# jkGate.net
KiCad netlist of a schematic drawn in EAGLE
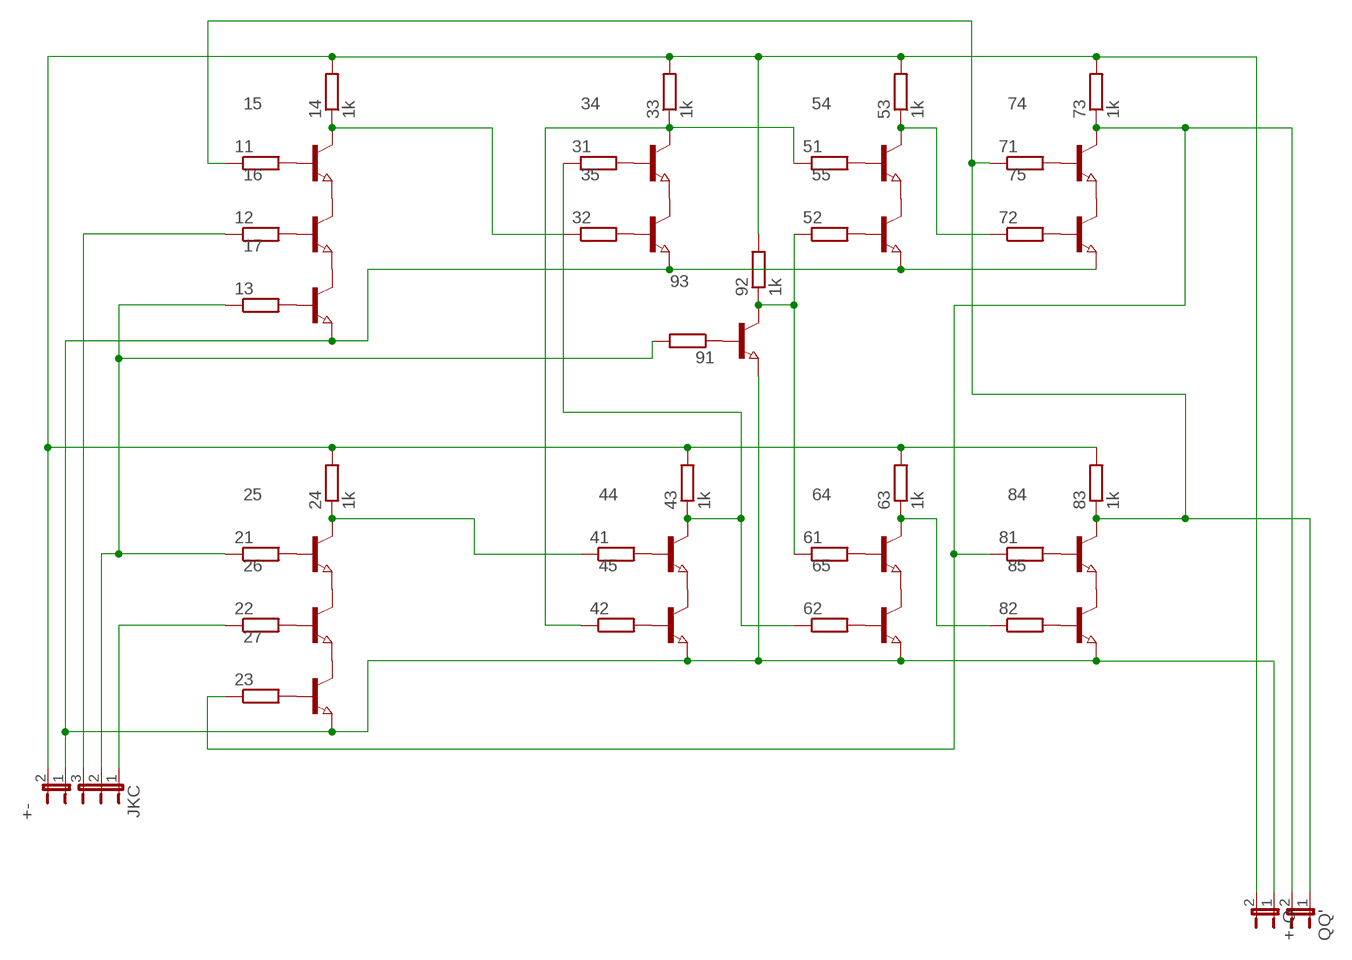
[diagram p0: schematic, sheet 1]

(export (version "E")
  (design (tool "Eeschema 10.0.6"))
  (components
    (comp (ref "+-")
      (value "JP1E")
      (footprint "eagle-import:JP1")
      (libsource (lib "eagle-import") (part "JP1E"))
    )
    (comp (ref "+-O")
      (value "JP1E")
      (footprint "eagle-import:JP1")
      (libsource (lib "eagle-import") (part "JP1E"))
    )
    (comp (ref "11")
      (value "R-EU_R1206")
      (footprint "eagle-import:R1206")
      (libsource (lib "eagle-import") (part "R-EU_R1206"))
    )
    (comp (ref "12")
      (value "R-EU_R1206")
      (footprint "eagle-import:R1206")
      (libsource (lib "eagle-import") (part "R-EU_R1206"))
    )
    (comp (ref "13")
      (value "R-EU_R1206")
      (footprint "eagle-import:R1206")
      (libsource (lib "eagle-import") (part "R-EU_R1206"))
    )
    (comp (ref "14")
      (value "1k")
      (footprint "eagle-import:R1206")
      (libsource (lib "eagle-import") (part "R-EU_R1206"))
    )
    (comp (ref "15")
      (value "NPN-TRANSISTOR_SOT23")
      (footprint "eagle-import:SOT23")
      (libsource (lib "eagle-import") (part "NPN-TRANSISTOR_SOT23"))
    )
    (comp (ref "16")
      (value "NPN-TRANSISTOR_SOT23")
      (footprint "eagle-import:SOT23")
      (libsource (lib "eagle-import") (part "NPN-TRANSISTOR_SOT23"))
    )
    (comp (ref "17")
      (value "NPN-TRANSISTOR_SOT23")
      (footprint "eagle-import:SOT23")
      (libsource (lib "eagle-import") (part "NPN-TRANSISTOR_SOT23"))
    )
    (comp (ref "21")
      (value "R-EU_R1206")
      (footprint "eagle-import:R1206")
      (libsource (lib "eagle-import") (part "R-EU_R1206"))
    )
    (comp (ref "22")
      (value "R-EU_R1206")
      (footprint "eagle-import:R1206")
      (libsource (lib "eagle-import") (part "R-EU_R1206"))
    )
    (comp (ref "23")
      (value "R-EU_R1206")
      (footprint "eagle-import:R1206")
      (libsource (lib "eagle-import") (part "R-EU_R1206"))
    )
    (comp (ref "24")
      (value "1k")
      (footprint "eagle-import:R1206")
      (libsource (lib "eagle-import") (part "R-EU_R1206"))
    )
    (comp (ref "25")
      (value "NPN-TRANSISTOR_SOT23")
      (footprint "eagle-import:SOT23")
      (libsource (lib "eagle-import") (part "NPN-TRANSISTOR_SOT23"))
    )
    (comp (ref "26")
      (value "NPN-TRANSISTOR_SOT23")
      (footprint "eagle-import:SOT23")
      (libsource (lib "eagle-import") (part "NPN-TRANSISTOR_SOT23"))
    )
    (comp (ref "27")
      (value "NPN-TRANSISTOR_SOT23")
      (footprint "eagle-import:SOT23")
      (libsource (lib "eagle-import") (part "NPN-TRANSISTOR_SOT23"))
    )
    (comp (ref "31")
      (value "R-EU_R1206")
      (footprint "eagle-import:R1206")
      (libsource (lib "eagle-import") (part "R-EU_R1206"))
    )
    (comp (ref "32")
      (value "R-EU_R1206")
      (footprint "eagle-import:R1206")
      (libsource (lib "eagle-import") (part "R-EU_R1206"))
    )
    (comp (ref "33")
      (value "1k")
      (footprint "eagle-import:R1206")
      (libsource (lib "eagle-import") (part "R-EU_R1206"))
    )
    (comp (ref "34")
      (value "NPN-TRANSISTOR_SOT23")
      (footprint "eagle-import:SOT23")
      (libsource (lib "eagle-import") (part "NPN-TRANSISTOR_SOT23"))
    )
    (comp (ref "35")
      (value "NPN-TRANSISTOR_SOT23")
      (footprint "eagle-import:SOT23")
      (libsource (lib "eagle-import") (part "NPN-TRANSISTOR_SOT23"))
    )
    (comp (ref "41")
      (value "R-EU_R1206")
      (footprint "eagle-import:R1206")
      (libsource (lib "eagle-import") (part "R-EU_R1206"))
    )
    (comp (ref "42")
      (value "R-EU_R1206")
      (footprint "eagle-import:R1206")
      (libsource (lib "eagle-import") (part "R-EU_R1206"))
    )
    (comp (ref "43")
      (value "1k")
      (footprint "eagle-import:R1206")
      (libsource (lib "eagle-import") (part "R-EU_R1206"))
    )
    (comp (ref "44")
      (value "NPN-TRANSISTOR_SOT23")
      (footprint "eagle-import:SOT23")
      (libsource (lib "eagle-import") (part "NPN-TRANSISTOR_SOT23"))
    )
    (comp (ref "45")
      (value "NPN-TRANSISTOR_SOT23")
      (footprint "eagle-import:SOT23")
      (libsource (lib "eagle-import") (part "NPN-TRANSISTOR_SOT23"))
    )
    (comp (ref "51")
      (value "R-EU_R1206")
      (footprint "eagle-import:R1206")
      (libsource (lib "eagle-import") (part "R-EU_R1206"))
    )
    (comp (ref "52")
      (value "R-EU_R1206")
      (footprint "eagle-import:R1206")
      (libsource (lib "eagle-import") (part "R-EU_R1206"))
    )
    (comp (ref "53")
      (value "1k")
      (footprint "eagle-import:R1206")
      (libsource (lib "eagle-import") (part "R-EU_R1206"))
    )
    (comp (ref "54")
      (value "NPN-TRANSISTOR_SOT23")
      (footprint "eagle-import:SOT23")
      (libsource (lib "eagle-import") (part "NPN-TRANSISTOR_SOT23"))
    )
    (comp (ref "55")
      (value "NPN-TRANSISTOR_SOT23")
      (footprint "eagle-import:SOT23")
      (libsource (lib "eagle-import") (part "NPN-TRANSISTOR_SOT23"))
    )
    (comp (ref "61")
      (value "R-EU_R1206")
      (footprint "eagle-import:R1206")
      (libsource (lib "eagle-import") (part "R-EU_R1206"))
    )
    (comp (ref "62")
      (value "R-EU_R1206")
      (footprint "eagle-import:R1206")
      (libsource (lib "eagle-import") (part "R-EU_R1206"))
    )
    (comp (ref "63")
      (value "1k")
      (footprint "eagle-import:R1206")
      (libsource (lib "eagle-import") (part "R-EU_R1206"))
    )
    (comp (ref "64")
      (value "NPN-TRANSISTOR_SOT23")
      (footprint "eagle-import:SOT23")
      (libsource (lib "eagle-import") (part "NPN-TRANSISTOR_SOT23"))
    )
    (comp (ref "65")
      (value "NPN-TRANSISTOR_SOT23")
      (footprint "eagle-import:SOT23")
      (libsource (lib "eagle-import") (part "NPN-TRANSISTOR_SOT23"))
    )
    (comp (ref "71")
      (value "R-EU_R1206")
      (footprint "eagle-import:R1206")
      (libsource (lib "eagle-import") (part "R-EU_R1206"))
    )
    (comp (ref "72")
      (value "R-EU_R1206")
      (footprint "eagle-import:R1206")
      (libsource (lib "eagle-import") (part "R-EU_R1206"))
    )
    (comp (ref "73")
      (value "1k")
      (footprint "eagle-import:R1206")
      (libsource (lib "eagle-import") (part "R-EU_R1206"))
    )
    (comp (ref "74")
      (value "NPN-TRANSISTOR_SOT23")
      (footprint "eagle-import:SOT23")
      (libsource (lib "eagle-import") (part "NPN-TRANSISTOR_SOT23"))
    )
    (comp (ref "75")
      (value "NPN-TRANSISTOR_SOT23")
      (footprint "eagle-import:SOT23")
      (libsource (lib "eagle-import") (part "NPN-TRANSISTOR_SOT23"))
    )
    (comp (ref "81")
      (value "R-EU_R1206")
      (footprint "eagle-import:R1206")
      (libsource (lib "eagle-import") (part "R-EU_R1206"))
    )
    (comp (ref "82")
      (value "R-EU_R1206")
      (footprint "eagle-import:R1206")
      (libsource (lib "eagle-import") (part "R-EU_R1206"))
    )
    (comp (ref "83")
      (value "1k")
      (footprint "eagle-import:R1206")
      (libsource (lib "eagle-import") (part "R-EU_R1206"))
    )
    (comp (ref "84")
      (value "NPN-TRANSISTOR_SOT23")
      (footprint "eagle-import:SOT23")
      (libsource (lib "eagle-import") (part "NPN-TRANSISTOR_SOT23"))
    )
    (comp (ref "85")
      (value "NPN-TRANSISTOR_SOT23")
      (footprint "eagle-import:SOT23")
      (libsource (lib "eagle-import") (part "NPN-TRANSISTOR_SOT23"))
    )
    (comp (ref "91")
      (value "R-EU_R1206")
      (footprint "eagle-import:R1206")
      (libsource (lib "eagle-import") (part "R-EU_R1206"))
    )
    (comp (ref "92")
      (value "1k")
      (footprint "eagle-import:R1206")
      (libsource (lib "eagle-import") (part "R-EU_R1206"))
    )
    (comp (ref "93")
      (value "NPN-TRANSISTOR_SOT23")
      (footprint "eagle-import:SOT23")
      (libsource (lib "eagle-import") (part "NPN-TRANSISTOR_SOT23"))
    )
    (comp (ref "JKC")
      (value "JP2E")
      (footprint "eagle-import:JP2")
      (libsource (lib "eagle-import") (part "JP2E"))
    )
    (comp (ref "QQ'")
      (value "JP1E")
      (footprint "eagle-import:JP1")
      (libsource (lib "eagle-import") (part "JP1E"))
    )
  )
  (nets
    (net (code "1") (name "Net-(+--Pad2)") (class "Default")
      (node (ref "+-") (pin "2") (pinfunction "2_2") (pintype "passive"))
      (node (ref "+-O") (pin "2") (pinfunction "2_2") (pintype "passive"))
      (node (ref "14") (pin "2") (pinfunction "2_2") (pintype "passive"))
      (node (ref "24") (pin "2") (pinfunction "2_2") (pintype "passive"))
      (node (ref "33") (pin "2") (pinfunction "2_2") (pintype "passive"))
      (node (ref "43") (pin "2") (pinfunction "2_2") (pintype "passive"))
      (node (ref "53") (pin "2") (pinfunction "2_2") (pintype "passive"))
      (node (ref "63") (pin "2") (pinfunction "2_2") (pintype "passive"))
      (node (ref "73") (pin "2") (pinfunction "2_2") (pintype "passive"))
      (node (ref "83") (pin "2") (pinfunction "2_2") (pintype "passive"))
      (node (ref "92") (pin "2") (pinfunction "2_2") (pintype "passive"))
    )
    (net (code "2") (name "Net-(12-Pad1)") (class "Default")
      (node (ref "12") (pin "1") (pinfunction "1_1") (pintype "passive"))
      (node (ref "JKC") (pin "3") (pinfunction "3_3") (pintype "passive"))
    )
    (net (code "3") (name "Net-(13-Pad1)") (class "Default")
      (node (ref "13") (pin "1") (pinfunction "1_1") (pintype "passive"))
      (node (ref "21") (pin "1") (pinfunction "1_1") (pintype "passive"))
      (node (ref "91") (pin "2") (pinfunction "2_2") (pintype "passive"))
      (node (ref "JKC") (pin "2") (pinfunction "2_2") (pintype "passive"))
    )
    (net (code "4") (name "Net-(15-B)") (class "Default")
      (node (ref "11") (pin "2") (pinfunction "2_2") (pintype "passive"))
      (node (ref "15") (pin "1") (pinfunction "B_1") (pintype "passive"))
    )
    (net (code "5") (name "Net-(15-C)") (class "Default")
      (node (ref "14") (pin "1") (pinfunction "1_1") (pintype "passive"))
      (node (ref "15") (pin "3") (pinfunction "C_3") (pintype "passive"))
      (node (ref "32") (pin "1") (pinfunction "1_1") (pintype "passive"))
    )
    (net (code "6") (name "Net-(15-E)") (class "Default")
      (node (ref "15") (pin "2") (pinfunction "E_2") (pintype "passive"))
      (node (ref "16") (pin "3") (pinfunction "C_3") (pintype "passive"))
    )
    (net (code "7") (name "Net-(16-B)") (class "Default")
      (node (ref "12") (pin "2") (pinfunction "2_2") (pintype "passive"))
      (node (ref "16") (pin "1") (pinfunction "B_1") (pintype "passive"))
    )
    (net (code "8") (name "Net-(16-E)") (class "Default")
      (node (ref "16") (pin "2") (pinfunction "E_2") (pintype "passive"))
      (node (ref "17") (pin "3") (pinfunction "C_3") (pintype "passive"))
    )
    (net (code "9") (name "Net-(17-B)") (class "Default")
      (node (ref "13") (pin "2") (pinfunction "2_2") (pintype "passive"))
      (node (ref "17") (pin "1") (pinfunction "B_1") (pintype "passive"))
    )
    (net (code "10") (name "Net-(17-E)") (class "Default")
      (node (ref "+-") (pin "1") (pinfunction "1_1") (pintype "passive"))
      (node (ref "+-O") (pin "1") (pinfunction "1_1") (pintype "passive"))
      (node (ref "17") (pin "2") (pinfunction "E_2") (pintype "passive"))
      (node (ref "27") (pin "2") (pinfunction "E_2") (pintype "passive"))
      (node (ref "35") (pin "2") (pinfunction "E_2") (pintype "passive"))
      (node (ref "45") (pin "2") (pinfunction "E_2") (pintype "passive"))
      (node (ref "55") (pin "2") (pinfunction "E_2") (pintype "passive"))
      (node (ref "65") (pin "2") (pinfunction "E_2") (pintype "passive"))
      (node (ref "75") (pin "2") (pinfunction "E_2") (pintype "passive"))
      (node (ref "85") (pin "2") (pinfunction "E_2") (pintype "passive"))
      (node (ref "93") (pin "2") (pinfunction "E_2") (pintype "passive"))
    )
    (net (code "11") (name "Net-(22-Pad1)") (class "Default")
      (node (ref "22") (pin "1") (pinfunction "1_1") (pintype "passive"))
      (node (ref "JKC") (pin "1") (pinfunction "1_1") (pintype "passive"))
    )
    (net (code "12") (name "Net-(25-B)") (class "Default")
      (node (ref "21") (pin "2") (pinfunction "2_2") (pintype "passive"))
      (node (ref "25") (pin "1") (pinfunction "B_1") (pintype "passive"))
    )
    (net (code "13") (name "Net-(25-C)") (class "Default")
      (node (ref "24") (pin "1") (pinfunction "1_1") (pintype "passive"))
      (node (ref "25") (pin "3") (pinfunction "C_3") (pintype "passive"))
      (node (ref "41") (pin "1") (pinfunction "1_1") (pintype "passive"))
    )
    (net (code "14") (name "Net-(25-E)") (class "Default")
      (node (ref "25") (pin "2") (pinfunction "E_2") (pintype "passive"))
      (node (ref "26") (pin "3") (pinfunction "C_3") (pintype "passive"))
    )
    (net (code "15") (name "Net-(26-B)") (class "Default")
      (node (ref "22") (pin "2") (pinfunction "2_2") (pintype "passive"))
      (node (ref "26") (pin "1") (pinfunction "B_1") (pintype "passive"))
    )
    (net (code "16") (name "Net-(26-E)") (class "Default")
      (node (ref "26") (pin "2") (pinfunction "E_2") (pintype "passive"))
      (node (ref "27") (pin "3") (pinfunction "C_3") (pintype "passive"))
    )
    (net (code "17") (name "Net-(27-B)") (class "Default")
      (node (ref "23") (pin "2") (pinfunction "2_2") (pintype "passive"))
      (node (ref "27") (pin "1") (pinfunction "B_1") (pintype "passive"))
    )
    (net (code "18") (name "Net-(34-B)") (class "Default")
      (node (ref "31") (pin "2") (pinfunction "2_2") (pintype "passive"))
      (node (ref "34") (pin "1") (pinfunction "B_1") (pintype "passive"))
    )
    (net (code "19") (name "Net-(34-C)") (class "Default")
      (node (ref "33") (pin "1") (pinfunction "1_1") (pintype "passive"))
      (node (ref "34") (pin "3") (pinfunction "C_3") (pintype "passive"))
      (node (ref "42") (pin "1") (pinfunction "1_1") (pintype "passive"))
      (node (ref "51") (pin "1") (pinfunction "1_1") (pintype "passive"))
    )
    (net (code "20") (name "Net-(34-E)") (class "Default")
      (node (ref "34") (pin "2") (pinfunction "E_2") (pintype "passive"))
      (node (ref "35") (pin "3") (pinfunction "C_3") (pintype "passive"))
    )
    (net (code "21") (name "Net-(35-B)") (class "Default")
      (node (ref "32") (pin "2") (pinfunction "2_2") (pintype "passive"))
      (node (ref "35") (pin "1") (pinfunction "B_1") (pintype "passive"))
    )
    (net (code "22") (name "Net-(44-B)") (class "Default")
      (node (ref "41") (pin "2") (pinfunction "2_2") (pintype "passive"))
      (node (ref "44") (pin "1") (pinfunction "B_1") (pintype "passive"))
    )
    (net (code "23") (name "Net-(44-C)") (class "Default")
      (node (ref "31") (pin "1") (pinfunction "1_1") (pintype "passive"))
      (node (ref "43") (pin "1") (pinfunction "1_1") (pintype "passive"))
      (node (ref "44") (pin "3") (pinfunction "C_3") (pintype "passive"))
      (node (ref "62") (pin "1") (pinfunction "1_1") (pintype "passive"))
    )
    (net (code "24") (name "Net-(44-E)") (class "Default")
      (node (ref "44") (pin "2") (pinfunction "E_2") (pintype "passive"))
      (node (ref "45") (pin "3") (pinfunction "C_3") (pintype "passive"))
    )
    (net (code "25") (name "Net-(45-B)") (class "Default")
      (node (ref "42") (pin "2") (pinfunction "2_2") (pintype "passive"))
      (node (ref "45") (pin "1") (pinfunction "B_1") (pintype "passive"))
    )
    (net (code "26") (name "Net-(54-B)") (class "Default")
      (node (ref "51") (pin "2") (pinfunction "2_2") (pintype "passive"))
      (node (ref "54") (pin "1") (pinfunction "B_1") (pintype "passive"))
    )
    (net (code "27") (name "Net-(54-C)") (class "Default")
      (node (ref "53") (pin "1") (pinfunction "1_1") (pintype "passive"))
      (node (ref "54") (pin "3") (pinfunction "C_3") (pintype "passive"))
      (node (ref "72") (pin "1") (pinfunction "1_1") (pintype "passive"))
    )
    (net (code "28") (name "Net-(54-E)") (class "Default")
      (node (ref "54") (pin "2") (pinfunction "E_2") (pintype "passive"))
      (node (ref "55") (pin "3") (pinfunction "C_3") (pintype "passive"))
    )
    (net (code "29") (name "Net-(55-B)") (class "Default")
      (node (ref "52") (pin "2") (pinfunction "2_2") (pintype "passive"))
      (node (ref "55") (pin "1") (pinfunction "B_1") (pintype "passive"))
    )
    (net (code "30") (name "Net-(64-B)") (class "Default")
      (node (ref "61") (pin "2") (pinfunction "2_2") (pintype "passive"))
      (node (ref "64") (pin "1") (pinfunction "B_1") (pintype "passive"))
    )
    (net (code "31") (name "Net-(64-C)") (class "Default")
      (node (ref "63") (pin "1") (pinfunction "1_1") (pintype "passive"))
      (node (ref "64") (pin "3") (pinfunction "C_3") (pintype "passive"))
      (node (ref "82") (pin "1") (pinfunction "1_1") (pintype "passive"))
    )
    (net (code "32") (name "Net-(64-E)") (class "Default")
      (node (ref "64") (pin "2") (pinfunction "E_2") (pintype "passive"))
      (node (ref "65") (pin "3") (pinfunction "C_3") (pintype "passive"))
    )
    (net (code "33") (name "Net-(65-B)") (class "Default")
      (node (ref "62") (pin "2") (pinfunction "2_2") (pintype "passive"))
      (node (ref "65") (pin "1") (pinfunction "B_1") (pintype "passive"))
    )
    (net (code "34") (name "Net-(74-B)") (class "Default")
      (node (ref "71") (pin "2") (pinfunction "2_2") (pintype "passive"))
      (node (ref "74") (pin "1") (pinfunction "B_1") (pintype "passive"))
    )
    (net (code "35") (name "Net-(74-C)") (class "Default")
      (node (ref "23") (pin "1") (pinfunction "1_1") (pintype "passive"))
      (node (ref "73") (pin "1") (pinfunction "1_1") (pintype "passive"))
      (node (ref "74") (pin "3") (pinfunction "C_3") (pintype "passive"))
      (node (ref "81") (pin "1") (pinfunction "1_1") (pintype "passive"))
      (node (ref "QQ'") (pin "2") (pinfunction "2_2") (pintype "passive"))
    )
    (net (code "36") (name "Net-(74-E)") (class "Default")
      (node (ref "74") (pin "2") (pinfunction "E_2") (pintype "passive"))
      (node (ref "75") (pin "3") (pinfunction "C_3") (pintype "passive"))
    )
    (net (code "37") (name "Net-(75-B)") (class "Default")
      (node (ref "72") (pin "2") (pinfunction "2_2") (pintype "passive"))
      (node (ref "75") (pin "1") (pinfunction "B_1") (pintype "passive"))
    )
    (net (code "38") (name "Net-(84-B)") (class "Default")
      (node (ref "81") (pin "2") (pinfunction "2_2") (pintype "passive"))
      (node (ref "84") (pin "1") (pinfunction "B_1") (pintype "passive"))
    )
    (net (code "39") (name "Net-(84-C)") (class "Default")
      (node (ref "11") (pin "1") (pinfunction "1_1") (pintype "passive"))
      (node (ref "71") (pin "1") (pinfunction "1_1") (pintype "passive"))
      (node (ref "83") (pin "1") (pinfunction "1_1") (pintype "passive"))
      (node (ref "84") (pin "3") (pinfunction "C_3") (pintype "passive"))
      (node (ref "QQ'") (pin "1") (pinfunction "1_1") (pintype "passive"))
    )
    (net (code "40") (name "Net-(84-E)") (class "Default")
      (node (ref "84") (pin "2") (pinfunction "E_2") (pintype "passive"))
      (node (ref "85") (pin "3") (pinfunction "C_3") (pintype "passive"))
    )
    (net (code "41") (name "Net-(85-B)") (class "Default")
      (node (ref "82") (pin "2") (pinfunction "2_2") (pintype "passive"))
      (node (ref "85") (pin "1") (pinfunction "B_1") (pintype "passive"))
    )
    (net (code "42") (name "Net-(93-B)") (class "Default")
      (node (ref "91") (pin "1") (pinfunction "1_1") (pintype "passive"))
      (node (ref "93") (pin "1") (pinfunction "B_1") (pintype "passive"))
    )
    (net (code "43") (name "Net-(93-C)") (class "Default")
      (node (ref "52") (pin "1") (pinfunction "1_1") (pintype "passive"))
      (node (ref "61") (pin "1") (pinfunction "1_1") (pintype "passive"))
      (node (ref "92") (pin "1") (pinfunction "1_1") (pintype "passive"))
      (node (ref "93") (pin "3") (pinfunction "C_3") (pintype "passive"))
    )
  )
)
